# electret-mic-precision-rectifier.net
KiCad netlist of a schematic drawn in EAGLE
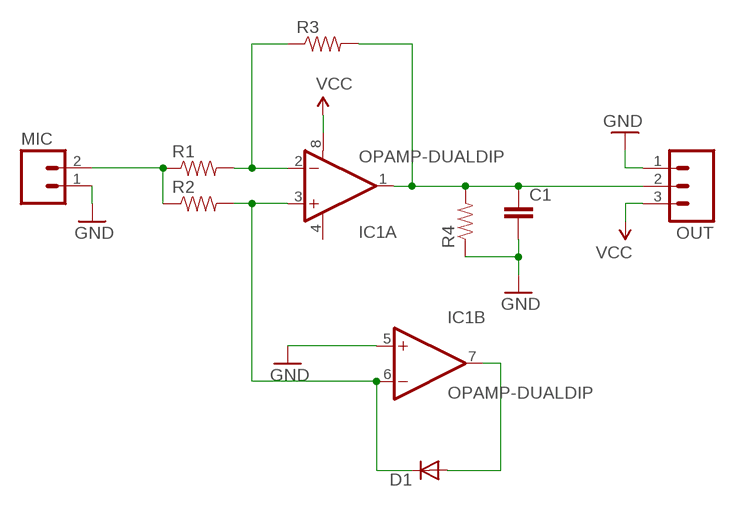
[diagram p0: schematic, sheet 1]

(export (version "E")
  (design (tool "Eeschema 10.0.6"))
  (components
    (comp (ref "C1")
      (value "CAP_")
      (footprint "eagle-import:AXIAL-5MM")
      (libsource (lib "eagle-import") (part "CAP_"))
    )
    (comp (ref "D1")
      (value "DIODEPTH")
      (footprint "eagle-import:DIODE-1N4001")
      (libsource (lib "eagle-import") (part "DIODEPTH"))
    )
    (comp (ref "IC1")
      (value "OPAMP-DUALDIP")
      (footprint "eagle-import:DIP08")
      (libsource (lib "eagle-import") (part "OPAMP-DUALDIP"))
    )
    (comp (ref "MIC")
      (value "M02PTH")
      (footprint "eagle-import:1X02")
      (libsource (lib "eagle-import") (part "M02PTH"))
    )
    (comp (ref "OUT")
      (value "M03PTH")
      (footprint "eagle-import:1X03")
      (libsource (lib "eagle-import") (part "M03PTH"))
    )
    (comp (ref "R1")
      (value "RESISTORPTH-1/6W")
      (footprint "eagle-import:1_6W-RES")
      (libsource (lib "eagle-import") (part "RESISTORPTH-1/6W"))
    )
    (comp (ref "R2")
      (value "RESISTORPTH-1/6W")
      (footprint "eagle-import:1_6W-RES")
      (libsource (lib "eagle-import") (part "RESISTORPTH-1/6W"))
    )
    (comp (ref "R3")
      (value "RESISTORPTH-1/6W")
      (footprint "eagle-import:1_6W-RES")
      (libsource (lib "eagle-import") (part "RESISTORPTH-1/6W"))
    )
    (comp (ref "R4")
      (value "RESISTORPTH-1/6W")
      (footprint "eagle-import:1_6W-RES")
      (libsource (lib "eagle-import") (part "RESISTORPTH-1/6W"))
    )
  )
  (nets
    (net (code "1") (name "/V-") (class "Default")
      (node (ref "IC1") (pin "4") (pinfunction "V-_4") (pintype "power_in"))
    )
    (net (code "2") (name "GND") (class "Default")
      (node (ref "C1") (pin "P$2") (pinfunction "2_P$2") (pintype "passive"))
      (node (ref "IC1") (pin "5") (pinfunction "+IN_5") (pintype "input"))
      (node (ref "MIC") (pin "1") (pinfunction "1_1") (pintype "passive"))
      (node (ref "OUT") (pin "1") (pinfunction "1_1") (pintype "passive"))
      (node (ref "R4") (pin "1") (pinfunction "1_1") (pintype "passive"))
    )
    (net (code "3") (name "Net-(C1-1)") (class "Default")
      (node (ref "C1") (pin "P$1") (pinfunction "1_P$1") (pintype "passive"))
      (node (ref "IC1") (pin "1") (pinfunction "OUT_1") (pintype "output"))
      (node (ref "OUT") (pin "2") (pinfunction "2_2") (pintype "passive"))
      (node (ref "R3") (pin "2") (pinfunction "2_2") (pintype "passive"))
      (node (ref "R4") (pin "2") (pinfunction "2_2") (pintype "passive"))
    )
    (net (code "4") (name "Net-(IC1A-+IN)") (class "Default")
      (node (ref "D1") (pin "C") (pinfunction "C_C") (pintype "passive"))
      (node (ref "IC1") (pin "3") (pinfunction "+IN_3") (pintype "input"))
      (node (ref "IC1") (pin "6") (pinfunction "-IN_6") (pintype "input"))
      (node (ref "R2") (pin "2") (pinfunction "2_2") (pintype "passive"))
    )
    (net (code "5") (name "Net-(IC1A--IN)") (class "Default")
      (node (ref "IC1") (pin "2") (pinfunction "-IN_2") (pintype "input"))
      (node (ref "R1") (pin "2") (pinfunction "2_2") (pintype "passive"))
      (node (ref "R3") (pin "1") (pinfunction "1_1") (pintype "passive"))
    )
    (net (code "6") (name "Net-(IC1B-OUT)") (class "Default")
      (node (ref "D1") (pin "A") (pinfunction "A_A") (pintype "passive"))
      (node (ref "IC1") (pin "7") (pinfunction "OUT_7") (pintype "output"))
    )
    (net (code "7") (name "Net-(MIC-Pad2)") (class "Default")
      (node (ref "MIC") (pin "2") (pinfunction "2_2") (pintype "passive"))
      (node (ref "R1") (pin "1") (pinfunction "1_1") (pintype "passive"))
      (node (ref "R2") (pin "1") (pinfunction "1_1") (pintype "passive"))
    )
    (net (code "8") (name "VCC") (class "Default")
      (node (ref "IC1") (pin "8") (pinfunction "V+_8") (pintype "power_in"))
      (node (ref "OUT") (pin "3") (pinfunction "3_3") (pintype "passive"))
    )
  )
)
